# sc.net
KiCad netlist of a schematic drawn in EAGLE
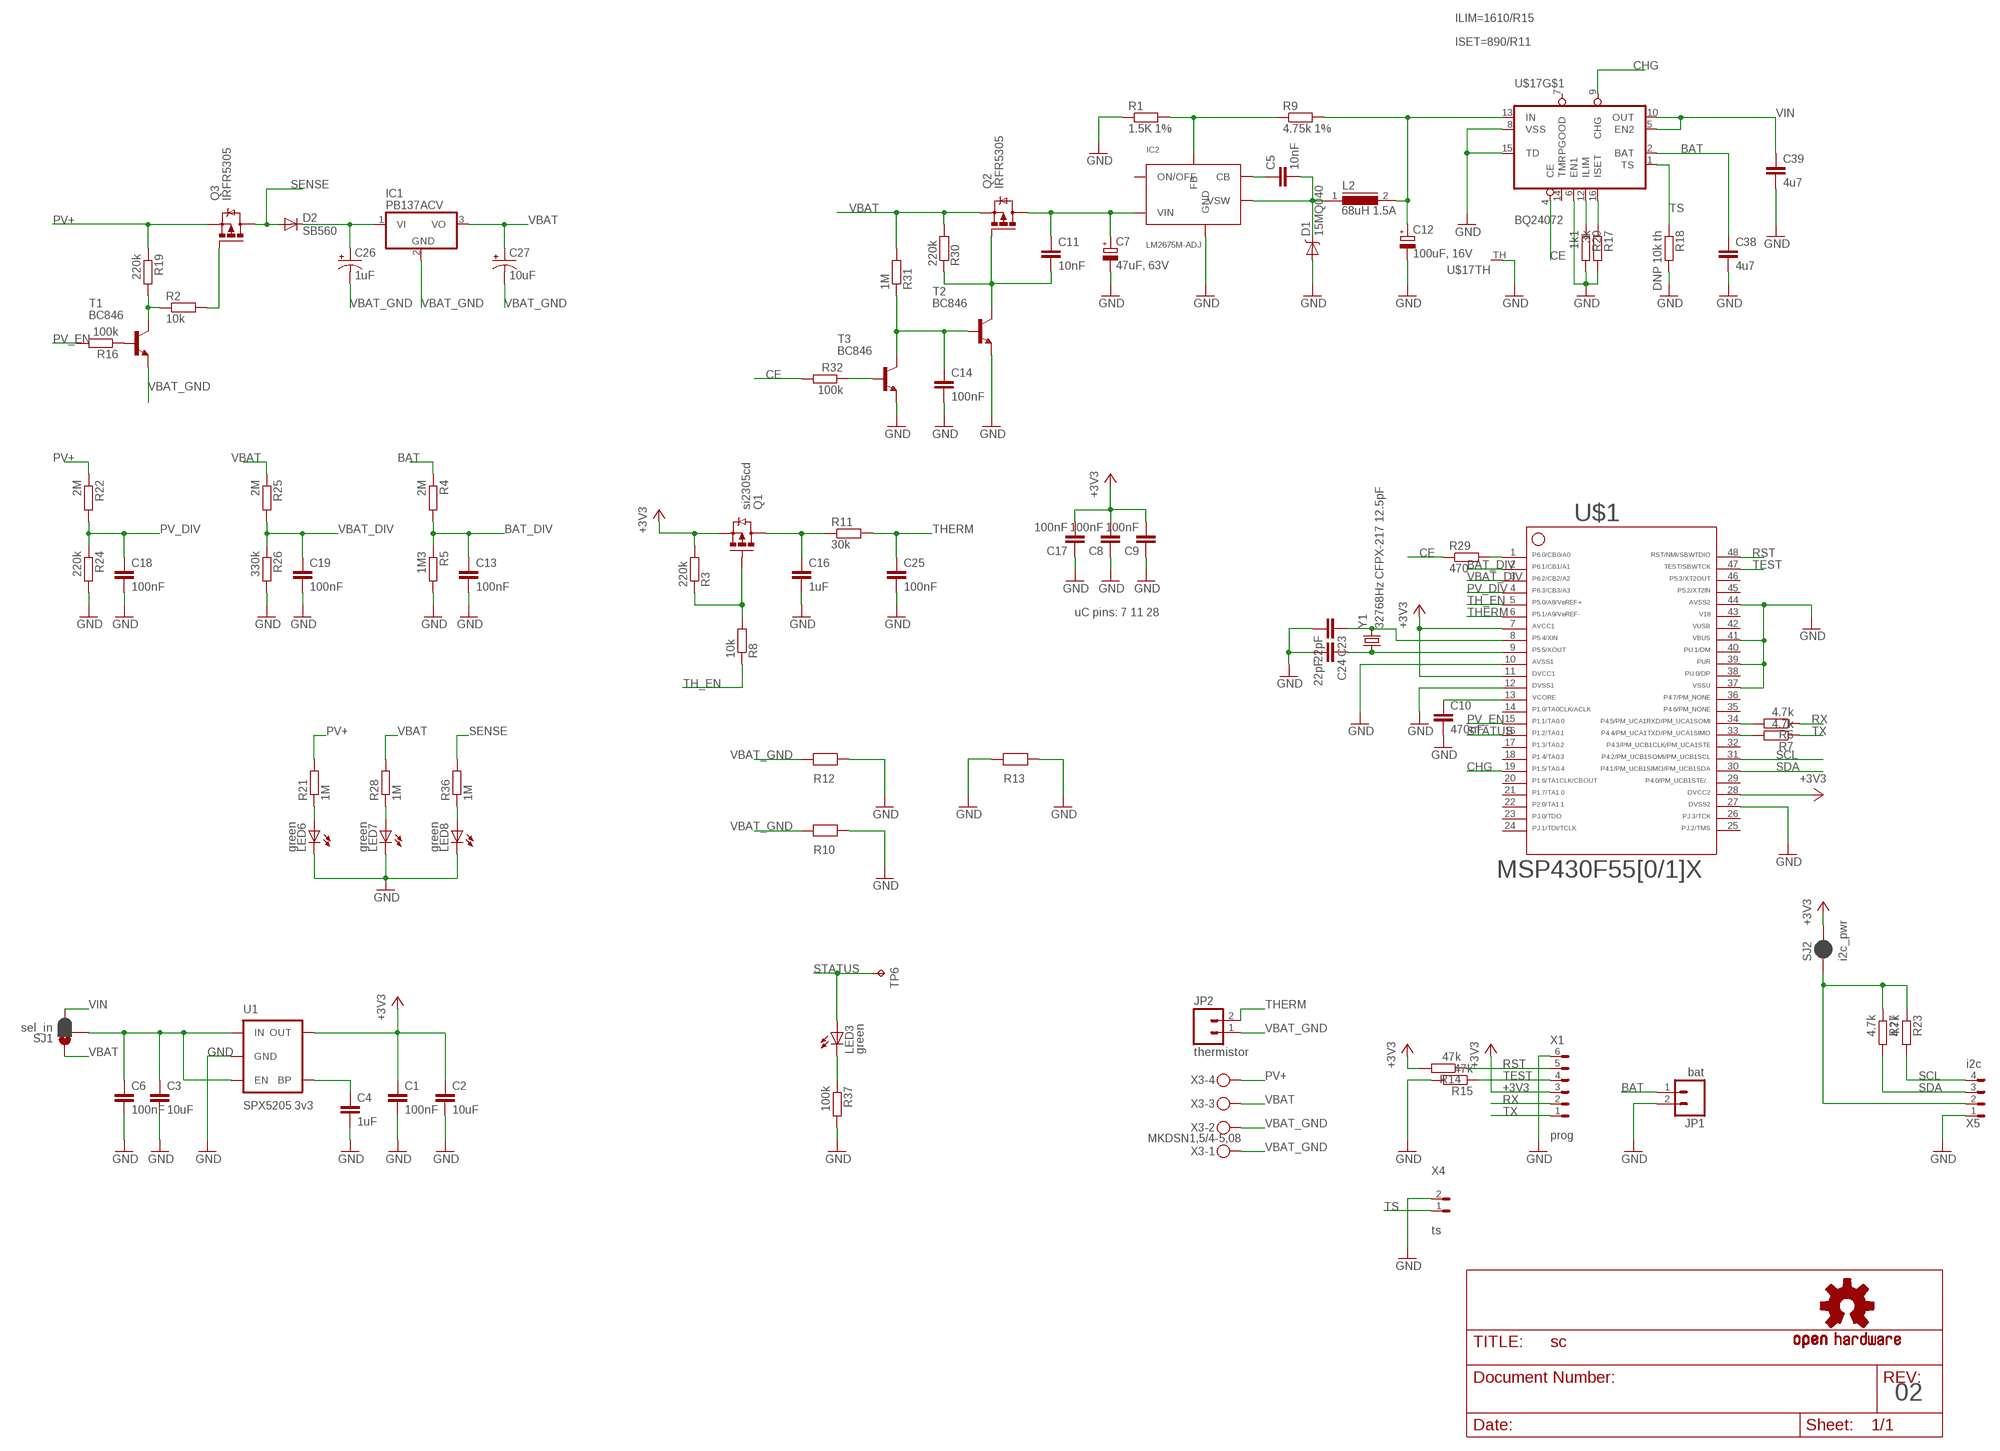
[diagram p0: schematic, sheet 1]

(export (version "E")
  (design (tool "Eeschema 10.0.6"))
  (components
    (comp (ref "C1")
      (value "100nF")
      (footprint "eagle-import:C0805")
      (libsource (lib "eagle-import") (part "C-EUC0805"))
    )
    (comp (ref "C2")
      (value "10uF")
      (footprint "eagle-import:C1206")
      (libsource (lib "eagle-import") (part "C-EUC1206"))
    )
    (comp (ref "C3")
      (value "10uF")
      (footprint "eagle-import:C1206")
      (libsource (lib "eagle-import") (part "C-EUC1206"))
    )
    (comp (ref "C4")
      (value "1uF")
      (footprint "eagle-import:C0805")
      (libsource (lib "eagle-import") (part "C-EUC0805"))
    )
    (comp (ref "C5")
      (value "10nF")
      (footprint "eagle-import:C0805")
      (libsource (lib "eagle-import") (part "C-EUC0805"))
    )
    (comp (ref "C6")
      (value "100nF")
      (footprint "eagle-import:C0805")
      (libsource (lib "eagle-import") (part "C-EUC0805"))
    )
    (comp (ref "C7")
      (value "47uF, 63V")
      (footprint "eagle-import:PANASONIC_F")
      (libsource (lib "eagle-import") (part "CPOL-EUF"))
    )
    (comp (ref "C8")
      (value "100nF")
      (footprint "eagle-import:C0805")
      (libsource (lib "eagle-import") (part "C-EUC0805"))
    )
    (comp (ref "C9")
      (value "100nF")
      (footprint "eagle-import:C0805")
      (libsource (lib "eagle-import") (part "C-EUC0805"))
    )
    (comp (ref "C10")
      (value "470nF")
      (footprint "eagle-import:C0805")
      (libsource (lib "eagle-import") (part "C-EUC0805"))
    )
    (comp (ref "C11")
      (value "10nF")
      (footprint "eagle-import:C0805")
      (libsource (lib "eagle-import") (part "C-EUC0805"))
    )
    (comp (ref "C12")
      (value "100uF, 16V")
      (footprint "eagle-import:PANASONIC_D")
      (libsource (lib "eagle-import") (part "CPOL-EUD"))
    )
    (comp (ref "C13")
      (value "100nF")
      (footprint "eagle-import:C0805")
      (libsource (lib "eagle-import") (part "C-EUC0805"))
    )
    (comp (ref "C14")
      (value "100nF")
      (footprint "eagle-import:C0805")
      (libsource (lib "eagle-import") (part "C-EUC0805"))
    )
    (comp (ref "C16")
      (value "1uF")
      (footprint "eagle-import:C0805")
      (libsource (lib "eagle-import") (part "C-EUC0805"))
    )
    (comp (ref "C17")
      (value "100nF")
      (footprint "eagle-import:C0805")
      (libsource (lib "eagle-import") (part "C-EUC0805"))
    )
    (comp (ref "C18")
      (value "100nF")
      (footprint "eagle-import:C0805")
      (libsource (lib "eagle-import") (part "C-EUC0805"))
    )
    (comp (ref "C19")
      (value "100nF")
      (footprint "eagle-import:C0805")
      (libsource (lib "eagle-import") (part "C-EUC0805"))
    )
    (comp (ref "C23")
      (value "22pF")
      (footprint "eagle-import:C0805")
      (libsource (lib "eagle-import") (part "C-EUC0805"))
    )
    (comp (ref "C24")
      (value "22pF")
      (footprint "eagle-import:C0805")
      (libsource (lib "eagle-import") (part "C-EUC0805"))
    )
    (comp (ref "C25")
      (value "100nF")
      (footprint "eagle-import:C0805")
      (libsource (lib "eagle-import") (part "C-EUC0805"))
    )
    (comp (ref "C26")
      (value "1uF")
      (footprint "eagle-import:PANASONIC_D")
      (libsource (lib "eagle-import") (part "CAP_POLD"))
    )
    (comp (ref "C27")
      (value "10uF")
      (footprint "eagle-import:PANASONIC_D")
      (libsource (lib "eagle-import") (part "CAP_POLD"))
    )
    (comp (ref "C38")
      (value "4u7")
      (footprint "eagle-import:C1206")
      (libsource (lib "eagle-import") (part "C-EUC1206"))
    )
    (comp (ref "C39")
      (value "4u7")
      (footprint "eagle-import:C1206")
      (libsource (lib "eagle-import") (part "C-EUC1206"))
    )
    (comp (ref "D1")
      (value "15MQ040")
      (footprint "eagle-import:SMA-DIODE")
      (libsource (lib "eagle-import") (part "DIODE-SCHOTTKY-MBRA140"))
    )
    (comp (ref "D2")
      (value "SB560")
      (footprint "eagle-import:C1702-05")
      (libsource (lib "eagle-import") (part "DIODE-C1702-05"))
    )
    (comp (ref "IC1")
      (value "PB137ACV")
      (footprint "eagle-import:TO220V")
      (libsource (lib "eagle-import") (part "78TV12"))
    )
    (comp (ref "IC2")
      (value "LM2675M-ADJ")
      (footprint "eagle-import:SO-08")
      (libsource (lib "eagle-import") (part "LM2674"))
    )
    (comp (ref "JP1")
      (value "bat")
      (footprint "eagle-import:1X02")
      (libsource (lib "eagle-import") (part "M02PTH"))
    )
    (comp (ref "JP2")
      (value "thermistor")
      (footprint "eagle-import:1X02")
      (libsource (lib "eagle-import") (part "M02PTH"))
    )
    (comp (ref "L2")
      (value "68uH 1.5A")
      (footprint "eagle-import:DR125")
      (libsource (lib "eagle-import") (part "DR125"))
    )
    (comp (ref "LED3")
      (value "green")
      (footprint "eagle-import:CHIPLED_0805")
      (libsource (lib "eagle-import") (part "LEDCHIPLED_0805"))
    )
    (comp (ref "LED6")
      (value "green")
      (footprint "eagle-import:CHIP-LED0805")
      (libsource (lib "eagle-import") (part "LEDCHIP-LED0805"))
    )
    (comp (ref "LED7")
      (value "green")
      (footprint "eagle-import:CHIP-LED0805")
      (libsource (lib "eagle-import") (part "LEDCHIP-LED0805"))
    )
    (comp (ref "LED8")
      (value "green")
      (footprint "eagle-import:CHIP-LED0805")
      (libsource (lib "eagle-import") (part "LEDCHIP-LED0805"))
    )
    (comp (ref "Q1")
      (value "si2305cd")
      (footprint "eagle-import:SOT23-3_POWER@1")
      (libsource (lib "eagle-import") (part "MOSFET-PCHANNELSMD_POWER"))
    )
    (comp (ref "Q2")
      (value "IRFR5305")
      (footprint "eagle-import:D-PAK_TO252AA")
      (libsource (lib "eagle-import") (part "IRF?5305R"))
    )
    (comp (ref "Q3")
      (value "IRFR5305")
      (footprint "eagle-import:D-PAK_TO252AA")
      (libsource (lib "eagle-import") (part "IRF?5305R"))
    )
    (comp (ref "R1")
      (value "1.5K 1%")
      (footprint "eagle-import:R0805W")
      (libsource (lib "eagle-import") (part "R-EU_R0805W"))
    )
    (comp (ref "R2")
      (value "10k")
      (footprint "eagle-import:R0805W")
      (libsource (lib "eagle-import") (part "R-EU_R0805W"))
    )
    (comp (ref "R3")
      (value "220k")
      (footprint "eagle-import:R0805W")
      (libsource (lib "eagle-import") (part "R-EU_R0805W"))
    )
    (comp (ref "R4")
      (value "2M")
      (footprint "eagle-import:R0805W")
      (libsource (lib "eagle-import") (part "R-EU_R0805W"))
    )
    (comp (ref "R5")
      (value "1M3")
      (footprint "eagle-import:R0805W")
      (libsource (lib "eagle-import") (part "R-EU_R0805W"))
    )
    (comp (ref "R6")
      (value "4.7k")
      (footprint "eagle-import:R0805W")
      (libsource (lib "eagle-import") (part "R-EU_R0805W"))
    )
    (comp (ref "R7")
      (value "4.7k")
      (footprint "eagle-import:R0805W")
      (libsource (lib "eagle-import") (part "R-EU_R0805W"))
    )
    (comp (ref "R8")
      (value "10k")
      (footprint "eagle-import:R0805W")
      (libsource (lib "eagle-import") (part "R-EU_R0805W"))
    )
    (comp (ref "R9")
      (value "4.75k 1%")
      (footprint "eagle-import:R0805W")
      (libsource (lib "eagle-import") (part "R-EU_R0805W"))
    )
    (comp (ref "R10")
      (value "0R_0805")
      (footprint "eagle-import:R0805W")
      (libsource (lib "eagle-import") (part "0R_0805"))
    )
    (comp (ref "R11")
      (value "30k")
      (footprint "eagle-import:R0805W")
      (libsource (lib "eagle-import") (part "R-EU_R0805W"))
    )
    (comp (ref "R12")
      (value "0R_0805")
      (footprint "eagle-import:R0805W")
      (libsource (lib "eagle-import") (part "0R_0805"))
    )
    (comp (ref "R13")
      (value "0R_0805")
      (footprint "eagle-import:R0805W")
      (libsource (lib "eagle-import") (part "0R_0805"))
    )
    (comp (ref "R14")
      (value "47k")
      (footprint "eagle-import:R0805W")
      (libsource (lib "eagle-import") (part "R-EU_R0805W"))
    )
    (comp (ref "R15")
      (value "47k")
      (footprint "eagle-import:R0805W")
      (libsource (lib "eagle-import") (part "R-EU_R0805W"))
    )
    (comp (ref "R16")
      (value "100k")
      (footprint "eagle-import:R0805W")
      (libsource (lib "eagle-import") (part "R-EU_R0805W"))
    )
    (comp (ref "R17")
      (value "3k")
      (footprint "eagle-import:R0805W")
      (libsource (lib "eagle-import") (part "R-EU_R0805W"))
    )
    (comp (ref "R18")
      (value "DNP 10k th")
      (footprint "eagle-import:R0805W")
      (libsource (lib "eagle-import") (part "R-EU_R0805W"))
    )
    (comp (ref "R19")
      (value "220k")
      (footprint "eagle-import:R0805W")
      (libsource (lib "eagle-import") (part "R-EU_R0805W"))
    )
    (comp (ref "R20")
      (value "1k1")
      (footprint "eagle-import:R0805W")
      (libsource (lib "eagle-import") (part "R-EU_R0805W"))
    )
    (comp (ref "R21")
      (value "1M")
      (footprint "eagle-import:R0805W")
      (libsource (lib "eagle-import") (part "R-EU_R0805W"))
    )
    (comp (ref "R22")
      (value "2M")
      (footprint "eagle-import:R0805W")
      (libsource (lib "eagle-import") (part "R-EU_R0805W"))
    )
    (comp (ref "R23")
      (value "4.7k")
      (footprint "eagle-import:R0805W")
      (libsource (lib "eagle-import") (part "R-EU_R0805W"))
    )
    (comp (ref "R24")
      (value "220k")
      (footprint "eagle-import:R0805W")
      (libsource (lib "eagle-import") (part "R-EU_R0805W"))
    )
    (comp (ref "R25")
      (value "2M")
      (footprint "eagle-import:R0805W")
      (libsource (lib "eagle-import") (part "R-EU_R0805W"))
    )
    (comp (ref "R26")
      (value "330k")
      (footprint "eagle-import:R0805W")
      (libsource (lib "eagle-import") (part "R-EU_R0805W"))
    )
    (comp (ref "R27")
      (value "4.7k")
      (footprint "eagle-import:R0805W")
      (libsource (lib "eagle-import") (part "R-EU_R0805W"))
    )
    (comp (ref "R28")
      (value "1M")
      (footprint "eagle-import:R0805W")
      (libsource (lib "eagle-import") (part "R-EU_R0805W"))
    )
    (comp (ref "R29")
      (value "470")
      (footprint "eagle-import:R0805W")
      (libsource (lib "eagle-import") (part "R-EU_R0805W"))
    )
    (comp (ref "R30")
      (value "220k")
      (footprint "eagle-import:R0805W")
      (libsource (lib "eagle-import") (part "R-EU_R0805W"))
    )
    (comp (ref "R31")
      (value "1M")
      (footprint "eagle-import:R0805W")
      (libsource (lib "eagle-import") (part "R-EU_R0805W"))
    )
    (comp (ref "R32")
      (value "100k")
      (footprint "eagle-import:R0805W")
      (libsource (lib "eagle-import") (part "R-EU_R0805W"))
    )
    (comp (ref "R36")
      (value "1M")
      (footprint "eagle-import:R0805W")
      (libsource (lib "eagle-import") (part "R-EU_R0805W"))
    )
    (comp (ref "R37")
      (value "100k")
      (footprint "eagle-import:R0805W")
      (libsource (lib "eagle-import") (part "R-EU_R0805W"))
    )
    (comp (ref "SJ1")
      (value "sel_in")
      (footprint "eagle-import:PAD-JUMPER-3-2OF3_NC_BY_PASTE_YES_SILK_FULL_BOX")
      (libsource (lib "eagle-import") (part "JUMPER-PAD-3-2OF3_NC_BY_PASTE"))
    )
    (comp (ref "SJ2")
      (value "i2c_pwr")
      (footprint "eagle-import:PAD-JUMPER-2-NC_BY_PASTE_YES_SILK")
      (libsource (lib "eagle-import") (part "JUMPER-PAD-2-NC_BY_PASTE"))
    )
    (comp (ref "T1")
      (value "BC846")
      (footprint "eagle-import:SOT23")
      (libsource (lib "eagle-import") (part "BC846"))
    )
    (comp (ref "T2")
      (value "BC846")
      (footprint "eagle-import:SOT23")
      (libsource (lib "eagle-import") (part "BC846"))
    )
    (comp (ref "T3")
      (value "BC846")
      (footprint "eagle-import:SOT23")
      (libsource (lib "eagle-import") (part "BC846"))
    )
    (comp (ref "TP6")
      (value "TPTP12R")
      (footprint "eagle-import:TP12R")
      (libsource (lib "eagle-import") (part "TPTP12R"))
    )
    (comp (ref "U$1")
      (value "F55[0/1]X---PT48")
      (footprint "eagle-import:PT48")
      (libsource (lib "eagle-import") (part "F55[0/1]X---PT48"))
    )
    (comp (ref "U$7")
      (value "OSHW-LOGOM")
      (footprint "eagle-import:OSHW-LOGO-M")
      (libsource (lib "eagle-import") (part "OSHW-LOGOM"))
    )
    (comp (ref "U$17")
      (value "BQ24072")
      (footprint "eagle-import:S-PVQFN-N16")
      (libsource (lib "eagle-import") (part "BQ24072"))
    )
    (comp (ref "U1")
      (value "SPX5205 3v3")
      (footprint "eagle-import:SOT23-5")
      (libsource (lib "eagle-import") (part "V_REG_LDOSMD"))
    )
    (comp (ref "X1")
      (value "prog")
      (footprint "eagle-import:0530480610")
      (libsource (lib "eagle-import") (part "MOLEX_6HORIZONTAL"))
    )
    (comp (ref "X3")
      (value "MKDSN1,5/4-5,08")
      (footprint "eagle-import:MKDSN1,5_4-5,08")
      (fields (field (name "MPN") "SMKDSN1,5/4-5,08"))
      (libsource (lib "eagle-import") (part "MKDSN1,5/4-5,08"))
    )
    (comp (ref "X4")
      (value "ts")
      (footprint "eagle-import:0530480210")
      (libsource (lib "eagle-import") (part "MOLEX_2HORIZONTAL"))
    )
    (comp (ref "X5")
      (value "i2c")
      (footprint "eagle-import:0530480401")
      (libsource (lib "eagle-import") (part "MOLEX_4HORIZONTAL"))
    )
    (comp (ref "Y1")
      (value "32768Hz CFPX-217 12.5pF")
      (footprint "eagle-import:CRYSTAL-SMD-3.2X1.5")
      (libsource (lib "eagle-import") (part "CRYSTAL3.2X1.5"))
    )
  )
  (nets
    (net (code "1") (name "+3V3") (class "Default")
      (node (ref "C1") (pin "1") (pinfunction "1_1") (pintype "passive"))
      (node (ref "C17") (pin "2") (pinfunction "2_2") (pintype "passive"))
      (node (ref "C2") (pin "1") (pinfunction "1_1") (pintype "passive"))
      (node (ref "C8") (pin "2") (pinfunction "2_2") (pintype "passive"))
      (node (ref "C9") (pin "2") (pinfunction "2_2") (pintype "passive"))
      (node (ref "Q1") (pin "2") (pinfunction "S_2") (pintype "passive"))
      (node (ref "R14") (pin "2") (pinfunction "2_2") (pintype "passive"))
      (node (ref "R3") (pin "2") (pinfunction "2_2") (pintype "passive"))
      (node (ref "SJ2") (pin "2") (pinfunction "2_2") (pintype "passive"))
      (node (ref "U$1") (pin "11") (pinfunction "11_11") (pintype "power_in"))
      (node (ref "U$1") (pin "28") (pinfunction "28_28") (pintype "power_in"))
      (node (ref "U$1") (pin "7") (pinfunction "7_7") (pintype "power_in"))
      (node (ref "U1") (pin "5") (pinfunction "OUT_5") (pintype "passive"))
      (node (ref "X1") (pin "3") (pinfunction "4_3") (pintype "passive"))
    )
    (net (code "2") (name "/42") (class "Default")
      (node (ref "U$1") (pin "42") (pinfunction "42_42") (pintype "power_in"))
    )
    (net (code "3") (name "/43") (class "Default")
      (node (ref "U$1") (pin "43") (pinfunction "43_43") (pintype "power_in"))
    )
    (net (code "4") (name "/46") (class "Default")
      (node (ref "U$1") (pin "46") (pinfunction "46_46") (pintype "power_in"))
    )
    (net (code "5") (name "/BAT") (class "Default")
      (node (ref "C38") (pin "1") (pinfunction "1_1") (pintype "passive"))
      (node (ref "JP1") (pin "1") (pinfunction "1_1") (pintype "passive"))
      (node (ref "R4") (pin "1") (pinfunction "1_1") (pintype "passive"))
      (node (ref "U$17") (pin "2") (pinfunction "BAT_2") (pintype "input"))
    )
    (net (code "6") (name "/BAT_DIV") (class "Default")
      (node (ref "C13") (pin "1") (pinfunction "1_1") (pintype "passive"))
      (node (ref "R4") (pin "2") (pinfunction "2_2") (pintype "passive"))
      (node (ref "R5") (pin "1") (pinfunction "1_1") (pintype "passive"))
      (node (ref "U$1") (pin "2") (pinfunction "2_2") (pintype "bidirectional"))
    )
    (net (code "7") (name "/CE") (class "Default")
      (node (ref "R29") (pin "1") (pinfunction "1_1") (pintype "passive"))
      (node (ref "R32") (pin "2") (pinfunction "2_2") (pintype "passive"))
      (node (ref "U$17") (pin "4") (pinfunction "CE_4") (pintype "bidirectional"))
    )
    (net (code "8") (name "/CHG") (class "Default")
      (node (ref "U$1") (pin "19") (pinfunction "19_19") (pintype "bidirectional"))
      (node (ref "U$17") (pin "9") (pinfunction "CHG_9") (pintype "bidirectional"))
    )
    (net (code "9") (name "/PV+") (class "Default")
      (node (ref "Q3") (pin "3") (pinfunction "S_3") (pintype "passive"))
      (node (ref "R19") (pin "1") (pinfunction "1_1") (pintype "passive"))
      (node (ref "R21") (pin "2") (pinfunction "2_2") (pintype "passive"))
      (node (ref "R22") (pin "1") (pinfunction "1_1") (pintype "passive"))
      (node (ref "X3") (pin "4") (pinfunction "KL_4") (pintype "passive"))
    )
    (net (code "10") (name "/PV_DIV") (class "Default")
      (node (ref "C18") (pin "1") (pinfunction "1_1") (pintype "passive"))
      (node (ref "R22") (pin "2") (pinfunction "2_2") (pintype "passive"))
      (node (ref "R24") (pin "1") (pinfunction "1_1") (pintype "passive"))
      (node (ref "U$1") (pin "4") (pinfunction "4_4") (pintype "bidirectional"))
    )
    (net (code "11") (name "/PV_EN") (class "Default")
      (node (ref "R16") (pin "2") (pinfunction "2_2") (pintype "passive"))
      (node (ref "U$1") (pin "15") (pinfunction "15_15") (pintype "bidirectional"))
    )
    (net (code "12") (name "/RST") (class "Default")
      (node (ref "R14") (pin "1") (pinfunction "1_1") (pintype "passive"))
      (node (ref "U$1") (pin "48") (pinfunction "48_48") (pintype "bidirectional"))
      (node (ref "X1") (pin "5") (pinfunction "2_5") (pintype "passive"))
    )
    (net (code "13") (name "/RX") (class "Default")
      (node (ref "R6") (pin "1") (pinfunction "1_1") (pintype "passive"))
      (node (ref "X1") (pin "2") (pinfunction "5_2") (pintype "passive"))
    )
    (net (code "14") (name "/SCL") (class "Default")
      (node (ref "R23") (pin "2") (pinfunction "2_2") (pintype "passive"))
      (node (ref "U$1") (pin "31") (pinfunction "31_31") (pintype "bidirectional"))
      (node (ref "X5") (pin "4") (pinfunction "1_4") (pintype "passive"))
    )
    (net (code "15") (name "/SDA") (class "Default")
      (node (ref "R27") (pin "2") (pinfunction "2_2") (pintype "passive"))
      (node (ref "U$1") (pin "30") (pinfunction "30_30") (pintype "bidirectional"))
      (node (ref "X5") (pin "3") (pinfunction "2_3") (pintype "passive"))
    )
    (net (code "16") (name "/SENSE") (class "Default")
      (node (ref "D2") (pin "A") (pinfunction "A_A") (pintype "passive"))
      (node (ref "Q3") (pin "4") (pinfunction "D_4") (pintype "passive"))
      (node (ref "R36") (pin "2") (pinfunction "2_2") (pintype "passive"))
    )
    (net (code "17") (name "/STATUS") (class "Default")
      (node (ref "LED3") (pin "A") (pinfunction "A_A") (pintype "passive"))
      (node (ref "TP6") (pin "TP") (pinfunction "TP_TP") (pintype "input"))
      (node (ref "U$1") (pin "16") (pinfunction "16_16") (pintype "bidirectional"))
    )
    (net (code "18") (name "/TEST") (class "Default")
      (node (ref "R15") (pin "1") (pinfunction "1_1") (pintype "passive"))
      (node (ref "U$1") (pin "47") (pinfunction "47_47") (pintype "input"))
      (node (ref "X1") (pin "4") (pinfunction "3_4") (pintype "passive"))
    )
    (net (code "19") (name "/THERM") (class "Default")
      (node (ref "C25") (pin "1") (pinfunction "1_1") (pintype "passive"))
      (node (ref "JP2") (pin "2") (pinfunction "2_2") (pintype "passive"))
      (node (ref "R11") (pin "2") (pinfunction "2_2") (pintype "passive"))
      (node (ref "U$1") (pin "6") (pinfunction "6_6") (pintype "bidirectional"))
    )
    (net (code "20") (name "/TH_EN") (class "Default")
      (node (ref "R8") (pin "1") (pinfunction "1_1") (pintype "passive"))
      (node (ref "U$1") (pin "5") (pinfunction "5_5") (pintype "bidirectional"))
    )
    (net (code "21") (name "/TS") (class "Default")
      (node (ref "R18") (pin "1") (pinfunction "1_1") (pintype "passive"))
      (node (ref "U$17") (pin "1") (pinfunction "TS_1") (pintype "input"))
      (node (ref "X4") (pin "1") (pinfunction "2_1") (pintype "passive"))
    )
    (net (code "22") (name "/TX") (class "Default")
      (node (ref "R7") (pin "1") (pinfunction "1_1") (pintype "passive"))
      (node (ref "X1") (pin "1") (pinfunction "6_1") (pintype "passive"))
    )
    (net (code "23") (name "/VBAT") (class "Default")
      (node (ref "C27") (pin "+") (pinfunction "+_+") (pintype "passive"))
      (node (ref "IC1") (pin "3") (pinfunction "VO_3") (pintype "passive"))
      (node (ref "Q2") (pin "3") (pinfunction "S_3") (pintype "passive"))
      (node (ref "R25") (pin "1") (pinfunction "1_1") (pintype "passive"))
      (node (ref "R28") (pin "2") (pinfunction "2_2") (pintype "passive"))
      (node (ref "R30") (pin "2") (pinfunction "2_2") (pintype "passive"))
      (node (ref "R31") (pin "2") (pinfunction "2_2") (pintype "passive"))
      (node (ref "SJ1") (pin "1") (pinfunction "1_1") (pintype "passive"))
      (node (ref "X3") (pin "3") (pinfunction "KL_3") (pintype "passive"))
    )
    (net (code "24") (name "/VBAT_DIV") (class "Default")
      (node (ref "C19") (pin "1") (pinfunction "1_1") (pintype "passive"))
      (node (ref "R25") (pin "2") (pinfunction "2_2") (pintype "passive"))
      (node (ref "R26") (pin "1") (pinfunction "1_1") (pintype "passive"))
      (node (ref "U$1") (pin "3") (pinfunction "3_3") (pintype "bidirectional"))
    )
    (net (code "25") (name "/VBAT_GND") (class "Default")
      (node (ref "C26") (pin "-") (pinfunction "-_-") (pintype "passive"))
      (node (ref "C27") (pin "-") (pinfunction "-_-") (pintype "passive"))
      (node (ref "IC1") (pin "2") (pinfunction "GND_2") (pintype "passive"))
      (node (ref "JP2") (pin "1") (pinfunction "1_1") (pintype "passive"))
      (node (ref "R10") (pin "1") (pinfunction "P$1_1") (pintype "bidirectional"))
      (node (ref "R12") (pin "1") (pinfunction "P$1_1") (pintype "bidirectional"))
      (node (ref "T1") (pin "2") (pinfunction "E_2") (pintype "passive"))
      (node (ref "X3") (pin "1") (pinfunction "KL_1") (pintype "passive"))
      (node (ref "X3") (pin "2") (pinfunction "KL_2") (pintype "passive"))
    )
    (net (code "26") (name "/VIN") (class "Default")
      (node (ref "C39") (pin "1") (pinfunction "1_1") (pintype "passive"))
      (node (ref "SJ1") (pin "3") (pinfunction "3_3") (pintype "passive"))
      (node (ref "U$17") (pin "10") (pinfunction "OUT_10") (pintype "output"))
      (node (ref "U$17") (pin "5") (pinfunction "EN2_5") (pintype "input"))
    )
    (net (code "27") (name "GND") (class "Default")
      (node (ref "C1") (pin "2") (pinfunction "2_2") (pintype "passive"))
      (node (ref "C10") (pin "2") (pinfunction "2_2") (pintype "passive"))
      (node (ref "C12") (pin "-") (pinfunction "-_-") (pintype "passive"))
      (node (ref "C13") (pin "2") (pinfunction "2_2") (pintype "passive"))
      (node (ref "C14") (pin "2") (pinfunction "2_2") (pintype "passive"))
      (node (ref "C16") (pin "2") (pinfunction "2_2") (pintype "passive"))
      (node (ref "C17") (pin "1") (pinfunction "1_1") (pintype "passive"))
      (node (ref "C18") (pin "2") (pinfunction "2_2") (pintype "passive"))
      (node (ref "C19") (pin "2") (pinfunction "2_2") (pintype "passive"))
      (node (ref "C2") (pin "2") (pinfunction "2_2") (pintype "passive"))
      (node (ref "C23") (pin "2") (pinfunction "2_2") (pintype "passive"))
      (node (ref "C24") (pin "2") (pinfunction "2_2") (pintype "passive"))
      (node (ref "C25") (pin "2") (pinfunction "2_2") (pintype "passive"))
      (node (ref "C3") (pin "2") (pinfunction "2_2") (pintype "passive"))
      (node (ref "C38") (pin "2") (pinfunction "2_2") (pintype "passive"))
      (node (ref "C39") (pin "2") (pinfunction "2_2") (pintype "passive"))
      (node (ref "C4") (pin "2") (pinfunction "2_2") (pintype "passive"))
      (node (ref "C6") (pin "2") (pinfunction "2_2") (pintype "passive"))
      (node (ref "C7") (pin "-") (pinfunction "-_-") (pintype "passive"))
      (node (ref "C8") (pin "1") (pinfunction "1_1") (pintype "passive"))
      (node (ref "C9") (pin "1") (pinfunction "1_1") (pintype "passive"))
      (node (ref "D1") (pin "A") (pinfunction "A_A") (pintype "passive"))
      (node (ref "IC2") (pin "6") (pinfunction "GND_6") (pintype "bidirectional"))
      (node (ref "JP1") (pin "2") (pinfunction "2_2") (pintype "passive"))
      (node (ref "LED6") (pin "C") (pinfunction "C_C") (pintype "passive"))
      (node (ref "LED7") (pin "C") (pinfunction "C_C") (pintype "passive"))
      (node (ref "LED8") (pin "C") (pinfunction "C_C") (pintype "passive"))
      (node (ref "R1") (pin "1") (pinfunction "1_1") (pintype "passive"))
      (node (ref "R10") (pin "2") (pinfunction "P$2_2") (pintype "bidirectional"))
      (node (ref "R12") (pin "2") (pinfunction "P$2_2") (pintype "bidirectional"))
      (node (ref "R13") (pin "1") (pinfunction "P$1_1") (pintype "bidirectional"))
      (node (ref "R13") (pin "2") (pinfunction "P$2_2") (pintype "bidirectional"))
      (node (ref "R15") (pin "2") (pinfunction "2_2") (pintype "passive"))
      (node (ref "R17") (pin "2") (pinfunction "2_2") (pintype "passive"))
      (node (ref "R18") (pin "2") (pinfunction "2_2") (pintype "passive"))
      (node (ref "R20") (pin "2") (pinfunction "2_2") (pintype "passive"))
      (node (ref "R24") (pin "2") (pinfunction "2_2") (pintype "passive"))
      (node (ref "R26") (pin "2") (pinfunction "2_2") (pintype "passive"))
      (node (ref "R37") (pin "2") (pinfunction "2_2") (pintype "passive"))
      (node (ref "R5") (pin "2") (pinfunction "2_2") (pintype "passive"))
      (node (ref "T2") (pin "2") (pinfunction "E_2") (pintype "passive"))
      (node (ref "T3") (pin "2") (pinfunction "E_2") (pintype "passive"))
      (node (ref "U$1") (pin "10") (pinfunction "10_10") (pintype "power_in"))
      (node (ref "U$1") (pin "12") (pinfunction "12_12") (pintype "power_in"))
      (node (ref "U$1") (pin "27") (pinfunction "27_27") (pintype "power_in"))
      (node (ref "U$1") (pin "37") (pinfunction "37_37") (pintype "power_in"))
      (node (ref "U$1") (pin "39") (pinfunction "39_39") (pintype "bidirectional"))
      (node (ref "U$1") (pin "41") (pinfunction "41_41") (pintype "power_in"))
      (node (ref "U$1") (pin "44") (pinfunction "44_44") (pintype "power_in"))
      (node (ref "U$17") (pin "15") (pinfunction "TD_15") (pintype "bidirectional"))
      (node (ref "U$17") (pin "6") (pinfunction "EN1_6") (pintype "bidirectional"))
      (node (ref "U$17") (pin "8") (pinfunction "VSS_8") (pintype "power_in"))
      (node (ref "U$17") (pin "TH") (pinfunction "TH_TH") (pintype "passive"))
      (node (ref "U1") (pin "2") (pinfunction "GND_2") (pintype "input"))
      (node (ref "X1") (pin "6") (pinfunction "1_6") (pintype "passive"))
      (node (ref "X4") (pin "2") (pinfunction "1_2") (pintype "passive"))
      (node (ref "X5") (pin "1") (pinfunction "4_1") (pintype "passive"))
    )
    (net (code "28") (name "Net-(C10-Pad1)") (class "Default")
      (node (ref "C10") (pin "1") (pinfunction "1_1") (pintype "passive"))
      (node (ref "U$1") (pin "13") (pinfunction "13_13") (pintype "power_in"))
    )
    (net (code "29") (name "Net-(IC1-VI)") (class "Default")
      (node (ref "C26") (pin "+") (pinfunction "+_+") (pintype "passive"))
      (node (ref "D2") (pin "C") (pinfunction "C_C") (pintype "passive"))
      (node (ref "IC1") (pin "1") (pinfunction "VI_1") (pintype "input"))
    )
    (net (code "30") (name "Net-(IC2-CB)") (class "Default")
      (node (ref "C5") (pin "1") (pinfunction "1_1") (pintype "passive"))
      (node (ref "IC2") (pin "1") (pinfunction "CB_1") (pintype "bidirectional"))
    )
    (net (code "31") (name "Net-(IC2-FB)") (class "Default")
      (node (ref "IC2") (pin "4") (pinfunction "FB_4") (pintype "bidirectional"))
      (node (ref "R1") (pin "2") (pinfunction "2_2") (pintype "passive"))
      (node (ref "R9") (pin "1") (pinfunction "1_1") (pintype "passive"))
    )
    (net (code "32") (name "Net-(IC2-VIN)") (class "Default")
      (node (ref "C11") (pin "1") (pinfunction "1_1") (pintype "passive"))
      (node (ref "C7") (pin "+") (pinfunction "+_+") (pintype "passive"))
      (node (ref "IC2") (pin "7") (pinfunction "VIN_7") (pintype "bidirectional"))
      (node (ref "Q2") (pin "4") (pinfunction "D_4") (pintype "passive"))
    )
    (net (code "33") (name "Net-(IC2-VSW)") (class "Default")
      (node (ref "C5") (pin "2") (pinfunction "2_2") (pintype "passive"))
      (node (ref "D1") (pin "C") (pinfunction "C_C") (pintype "passive"))
      (node (ref "IC2") (pin "8") (pinfunction "VSW_8") (pintype "bidirectional"))
      (node (ref "L2") (pin "1") (pinfunction "1_1") (pintype "passive"))
    )
    (net (code "34") (name "Net-(LED3-PadC)") (class "Default")
      (node (ref "LED3") (pin "C") (pinfunction "C_C") (pintype "passive"))
      (node (ref "R37") (pin "1") (pinfunction "1_1") (pintype "passive"))
    )
    (net (code "35") (name "Net-(LED6-PadA)") (class "Default")
      (node (ref "LED6") (pin "A") (pinfunction "A_A") (pintype "passive"))
      (node (ref "R21") (pin "1") (pinfunction "1_1") (pintype "passive"))
    )
    (net (code "36") (name "Net-(LED7-PadA)") (class "Default")
      (node (ref "LED7") (pin "A") (pinfunction "A_A") (pintype "passive"))
      (node (ref "R28") (pin "1") (pinfunction "1_1") (pintype "passive"))
    )
    (net (code "37") (name "Net-(LED8-PadA)") (class "Default")
      (node (ref "LED8") (pin "A") (pinfunction "A_A") (pintype "passive"))
      (node (ref "R36") (pin "1") (pinfunction "1_1") (pintype "passive"))
    )
    (net (code "38") (name "Net-(Q1-D)") (class "Default")
      (node (ref "C16") (pin "1") (pinfunction "1_1") (pintype "passive"))
      (node (ref "Q1") (pin "3") (pinfunction "D_3") (pintype "passive"))
      (node (ref "R11") (pin "1") (pinfunction "1_1") (pintype "passive"))
    )
    (net (code "39") (name "Net-(Q1-G)") (class "Default")
      (node (ref "Q1") (pin "1") (pinfunction "G_1") (pintype "passive"))
      (node (ref "R3") (pin "1") (pinfunction "1_1") (pintype "passive"))
      (node (ref "R8") (pin "2") (pinfunction "2_2") (pintype "passive"))
    )
    (net (code "40") (name "Net-(Q2-G)") (class "Default")
      (node (ref "C11") (pin "2") (pinfunction "2_2") (pintype "passive"))
      (node (ref "Q2") (pin "1") (pinfunction "G_1") (pintype "passive"))
      (node (ref "R30") (pin "1") (pinfunction "1_1") (pintype "passive"))
      (node (ref "T2") (pin "3") (pinfunction "C_3") (pintype "passive"))
    )
    (net (code "41") (name "Net-(Q3-G)") (class "Default")
      (node (ref "Q3") (pin "1") (pinfunction "G_1") (pintype "passive"))
      (node (ref "R2") (pin "2") (pinfunction "2_2") (pintype "passive"))
    )
    (net (code "42") (name "Net-(R6-Pad2)") (class "Default")
      (node (ref "R6") (pin "2") (pinfunction "2_2") (pintype "passive"))
      (node (ref "U$1") (pin "34") (pinfunction "34_34") (pintype "bidirectional"))
    )
    (net (code "43") (name "Net-(R7-Pad2)") (class "Default")
      (node (ref "R7") (pin "2") (pinfunction "2_2") (pintype "passive"))
      (node (ref "U$1") (pin "33") (pinfunction "33_33") (pintype "bidirectional"))
    )
    (net (code "44") (name "Net-(R29-Pad2)") (class "Default")
      (node (ref "R29") (pin "2") (pinfunction "2_2") (pintype "passive"))
      (node (ref "U$1") (pin "1") (pinfunction "1_1") (pintype "bidirectional"))
    )
    (net (code "45") (name "Net-(T1-B)") (class "Default")
      (node (ref "R16") (pin "1") (pinfunction "1_1") (pintype "passive"))
      (node (ref "T1") (pin "1") (pinfunction "B_1") (pintype "passive"))
    )
    (net (code "46") (name "Net-(T1-C)") (class "Default")
      (node (ref "R19") (pin "2") (pinfunction "2_2") (pintype "passive"))
      (node (ref "R2") (pin "1") (pinfunction "1_1") (pintype "passive"))
      (node (ref "T1") (pin "3") (pinfunction "C_3") (pintype "passive"))
    )
    (net (code "47") (name "Net-(T2-B)") (class "Default")
      (node (ref "C14") (pin "1") (pinfunction "1_1") (pintype "passive"))
      (node (ref "R31") (pin "1") (pinfunction "1_1") (pintype "passive"))
      (node (ref "T2") (pin "1") (pinfunction "B_1") (pintype "passive"))
      (node (ref "T3") (pin "3") (pinfunction "C_3") (pintype "passive"))
    )
    (net (code "48") (name "Net-(T3-B)") (class "Default")
      (node (ref "R32") (pin "1") (pinfunction "1_1") (pintype "passive"))
      (node (ref "T3") (pin "1") (pinfunction "B_1") (pintype "passive"))
    )
    (net (code "49") (name "Net-(U$17A-ILIM)") (class "Default")
      (node (ref "R20") (pin "1") (pinfunction "1_1") (pintype "passive"))
      (node (ref "U$17") (pin "12") (pinfunction "ILIM_12") (pintype "bidirectional"))
    )
    (net (code "50") (name "Net-(U$17A-IN)") (class "Default")
      (node (ref "C12") (pin "+") (pinfunction "+_+") (pintype "passive"))
      (node (ref "L2") (pin "2") (pinfunction "2_2") (pintype "passive"))
      (node (ref "R9") (pin "2") (pinfunction "2_2") (pintype "passive"))
      (node (ref "U$17") (pin "13") (pinfunction "IN_13") (pintype "input"))
    )
    (net (code "51") (name "Net-(U$17A-ISET)") (class "Default")
      (node (ref "R17") (pin "1") (pinfunction "1_1") (pintype "passive"))
      (node (ref "U$17") (pin "16") (pinfunction "ISET_16") (pintype "input"))
    )
    (net (code "52") (name "Net-(U1-BP)") (class "Default")
      (node (ref "C4") (pin "1") (pinfunction "1_1") (pintype "passive"))
      (node (ref "U1") (pin "4") (pinfunction "BP_4") (pintype "input"))
    )
    (net (code "53") (name "Net-(U1-EN)") (class "Default")
      (node (ref "C3") (pin "1") (pinfunction "1_1") (pintype "passive"))
      (node (ref "C6") (pin "1") (pinfunction "1_1") (pintype "passive"))
      (node (ref "SJ1") (pin "2") (pinfunction "2_2") (pintype "passive"))
      (node (ref "U1") (pin "1") (pinfunction "IN_1") (pintype "input"))
      (node (ref "U1") (pin "3") (pinfunction "EN_3") (pintype "input"))
    )
    (net (code "54") (name "Net-(X5-3)") (class "Default")
      (node (ref "R23") (pin "1") (pinfunction "1_1") (pintype "passive"))
      (node (ref "R27") (pin "1") (pinfunction "1_1") (pintype "passive"))
      (node (ref "SJ2") (pin "1") (pinfunction "1_1") (pintype "passive"))
      (node (ref "X5") (pin "2") (pinfunction "3_2") (pintype "passive"))
    )
    (net (code "55") (name "Net-(Y1-1)") (class "Default")
      (node (ref "C24") (pin "1") (pinfunction "1_1") (pintype "passive"))
      (node (ref "U$1") (pin "9") (pinfunction "9_9") (pintype "bidirectional"))
      (node (ref "Y1") (pin "P$1") (pinfunction "1_P$1") (pintype "passive"))
    )
    (net (code "56") (name "Net-(Y1-2)") (class "Default")
      (node (ref "C23") (pin "1") (pinfunction "1_1") (pintype "passive"))
      (node (ref "U$1") (pin "8") (pinfunction "8_8") (pintype "bidirectional"))
      (node (ref "Y1") (pin "P$2") (pinfunction "2_P$2") (pintype "passive"))
    )
    (net (code "57") (name "unconnected-(IC2-ON{slash}OFF-Pad5)") (class "Default")
      (node (ref "IC2") (pin "5") (pinfunction "ON/OFF_5") (pintype "bidirectional"))
    )
    (net (code "58") (name "unconnected-(U$1-Pad14)") (class "Default")
      (node (ref "U$1") (pin "14") (pinfunction "14_14") (pintype "bidirectional"))
    )
    (net (code "59") (name "unconnected-(U$1-Pad17)") (class "Default")
      (node (ref "U$1") (pin "17") (pinfunction "17_17") (pintype "bidirectional"))
    )
    (net (code "60") (name "unconnected-(U$1-Pad18)") (class "Default")
      (node (ref "U$1") (pin "18") (pinfunction "18_18") (pintype "bidirectional"))
    )
    (net (code "61") (name "unconnected-(U$1-Pad20)") (class "Default")
      (node (ref "U$1") (pin "20") (pinfunction "20_20") (pintype "bidirectional"))
    )
    (net (code "62") (name "unconnected-(U$1-Pad21)") (class "Default")
      (node (ref "U$1") (pin "21") (pinfunction "21_21") (pintype "bidirectional"))
    )
    (net (code "63") (name "unconnected-(U$1-Pad22)") (class "Default")
      (node (ref "U$1") (pin "22") (pinfunction "22_22") (pintype "bidirectional"))
    )
    (net (code "64") (name "unconnected-(U$1-Pad23)") (class "Default")
      (node (ref "U$1") (pin "23") (pinfunction "23_23") (pintype "bidirectional"))
    )
    (net (code "65") (name "unconnected-(U$1-Pad24)") (class "Default")
      (node (ref "U$1") (pin "24") (pinfunction "24_24") (pintype "bidirectional"))
    )
    (net (code "66") (name "unconnected-(U$1-Pad25)") (class "Default")
      (node (ref "U$1") (pin "25") (pinfunction "25_25") (pintype "bidirectional"))
    )
    (net (code "67") (name "unconnected-(U$1-Pad26)") (class "Default")
      (node (ref "U$1") (pin "26") (pinfunction "26_26") (pintype "bidirectional"))
    )
    (net (code "68") (name "unconnected-(U$1-Pad29)") (class "Default")
      (node (ref "U$1") (pin "29") (pinfunction "29_29") (pintype "bidirectional"))
    )
    (net (code "69") (name "unconnected-(U$1-Pad32)") (class "Default")
      (node (ref "U$1") (pin "32") (pinfunction "32_32") (pintype "bidirectional"))
    )
    (net (code "70") (name "unconnected-(U$1-Pad35)") (class "Default")
      (node (ref "U$1") (pin "35") (pinfunction "35_35") (pintype "bidirectional"))
    )
    (net (code "71") (name "unconnected-(U$1-Pad36)") (class "Default")
      (node (ref "U$1") (pin "36") (pinfunction "36_36") (pintype "bidirectional"))
    )
    (net (code "72") (name "unconnected-(U$1-Pad38)") (class "Default")
      (node (ref "U$1") (pin "38") (pinfunction "38_38") (pintype "bidirectional"))
    )
    (net (code "73") (name "unconnected-(U$1-Pad40)") (class "Default")
      (node (ref "U$1") (pin "40") (pinfunction "40_40") (pintype "bidirectional"))
    )
    (net (code "74") (name "unconnected-(U$1-Pad45)") (class "Default")
      (node (ref "U$1") (pin "45") (pinfunction "45_45") (pintype "bidirectional"))
    )
    (net (code "75") (name "unconnected-(U$17A-PGOOD-Pad7)") (class "Default")
      (node (ref "U$17") (pin "7") (pinfunction "PGOOD_7") (pintype "bidirectional"))
    )
    (net (code "76") (name "unconnected-(U$17A-TMR-Pad14)") (class "Default")
      (node (ref "U$17") (pin "14") (pinfunction "TMR_14") (pintype "bidirectional"))
    )
  )
)
